# Pmod_DA4.net
KiCad netlist of a schematic drawn in Altium Designer
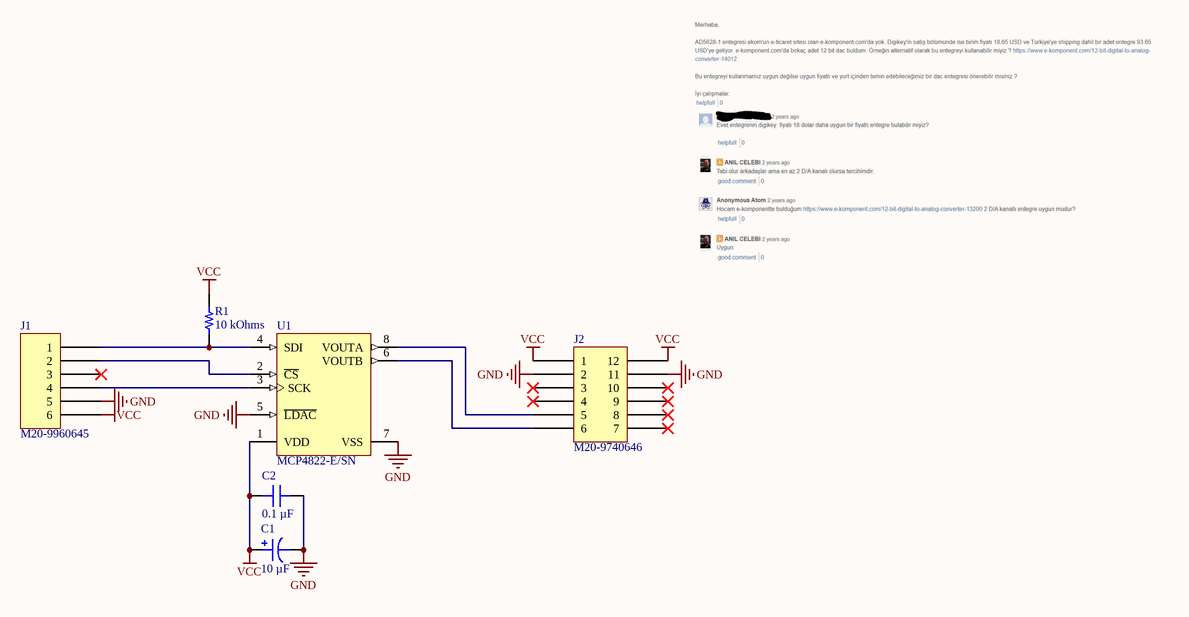
[diagram p0: Pmod_DA4.SchDoc]

(export (version "E")
  (design (tool "Eeschema 10.0.6"))
  (components
    (comp (ref "C1")
      (value "10 µF")
      (footprint "CAP POL 2917_7343")
      (description "CAP TANT 10UF 20% 50V 2917")
      (fields (field (name "PART NUMBER") "293D106X0050E2TE3") (field (name "MANUFACTURER") "Vishay Sprague"))
      (libsource (lib "Celestial Altium Library - altium_library") (part "Polarised Capacitor"))
    )
    (comp (ref "C2")
      (value "0.1 µF")
      (footprint "CAP 0805_2012")
      (description "CAP CER 0.1UF 50V X7R 0805")
      (fields (field (name "PART NUMBER") "CC0805MRX7R9BB104") (field (name "MANUFACTURER") "Yageo"))
      (libsource (lib "Celestial Altium Library - altium_library") (part "Capacitor"))
    )
    (comp (ref "J1")
      (value "M20-9960645")
      (footprint "HARWIN M20-9960645")
      (description "CONN HEADER R/A 6POS 2.54MM")
      (fields (field (name "MANUFACTURER") "Harwin Inc."))
      (libsource (lib "Celestial Altium Library - altium_library") (part "6 Pin"))
    )
    (comp (ref "J2")
      (value "M20-9740646")
      (footprint "HARWIN M20-9740645")
      (description "CONN HEADER R/A 12POS 2.54MM")
      (fields (field (name "MANUFACTURER") "Harwin Inc."))
      (libsource (lib "Celestial Altium Library - altium_library") (part "2X6 PIN DU"))
    )
    (comp (ref "R1")
      (value "10 kOhms")
      (footprint "RES 0805_2012")
      (description "TNPU0805 10K 0.05% 2PPM E52 E3")
      (fields (field (name "PART NUMBER") "TNPU080510K0AWEN00") (field (name "MANUFACTURER") "Vishay Dale"))
      (libsource (lib "Celestial Altium Library - altium_library") (part "Resistor"))
    )
    (comp (ref "U1")
      (value "MCP4822-E/SN")
      (footprint "SOIC-SN8_M")
      (description "12-Bit DACs with Internal VREF and SPI Interface, 8-Pin SOIC 150mil, Extended Temperature")
      (libsource (lib "Altium Content Vault") (part "CON-DAC-MCP4822-8"))
    )
  )
  (nets
    (net (code "1") (name "GND") (class "Default")
      (node (ref "C1") (pin "2") (pinfunction "2_2") (pintype "passive"))
      (node (ref "C2") (pin "1") (pinfunction "1_1") (pintype "passive"))
      (node (ref "J1") (pin "5") (pinfunction "5_5") (pintype "passive"))
      (node (ref "J2") (pin "11") (pinfunction "11_11") (pintype "passive"))
      (node (ref "J2") (pin "2") (pinfunction "2_2") (pintype "passive"))
      (node (ref "U1") (pin "5") (pinfunction "~{LDAC}_5") (pintype "input"))
      (node (ref "U1") (pin "7") (pinfunction "VSS_7") (pintype "power_in"))
    )
    (net (code "2") (name "Net-(U1-SCK)") (class "Default")
      (node (ref "J1") (pin "4") (pinfunction "4_4") (pintype "passive"))
      (node (ref "U1") (pin "3") (pinfunction "SCK_3") (pintype "input"))
    )
    (net (code "3") (name "Net-(U1-SDI)") (class "Default")
      (node (ref "J1") (pin "1") (pinfunction "1_1") (pintype "passive"))
      (node (ref "R1") (pin "1") (pinfunction "1_1") (pintype "passive"))
      (node (ref "U1") (pin "4") (pinfunction "SDI_4") (pintype "input"))
    )
    (net (code "4") (name "Net-(U1-VOUTA)") (class "Default")
      (node (ref "J2") (pin "5") (pinfunction "5_5") (pintype "passive"))
      (node (ref "U1") (pin "8") (pinfunction "VOUTA_8") (pintype "output"))
    )
    (net (code "5") (name "Net-(U1-VOUTB)") (class "Default")
      (node (ref "J2") (pin "6") (pinfunction "6_6") (pintype "passive"))
      (node (ref "U1") (pin "6") (pinfunction "VOUTB_6") (pintype "output"))
    )
    (net (code "6") (name "Net-(U1-~{CS})") (class "Default")
      (node (ref "J1") (pin "2") (pinfunction "2_2") (pintype "passive"))
      (node (ref "U1") (pin "2") (pinfunction "~{CS}_2") (pintype "input"))
    )
    (net (code "7") (name "VCC") (class "Default")
      (node (ref "C1") (pin "1") (pinfunction "1_1") (pintype "passive"))
      (node (ref "C2") (pin "2") (pinfunction "2_2") (pintype "passive"))
      (node (ref "J1") (pin "6") (pinfunction "6_6") (pintype "passive"))
      (node (ref "J2") (pin "1") (pinfunction "1_1") (pintype "passive"))
      (node (ref "J2") (pin "12") (pinfunction "12_12") (pintype "passive"))
      (node (ref "R1") (pin "2") (pinfunction "2_2") (pintype "passive"))
      (node (ref "U1") (pin "1") (pinfunction "VDD_1") (pintype "power_in"))
    )
    (net (code "8") (name "unconnected-(J1-Pad3)") (class "Default")
      (node (ref "J1") (pin "3") (pinfunction "3_3") (pintype "passive+no_connect"))
    )
    (net (code "9") (name "unconnected-(J2-Pad3)") (class "Default")
      (node (ref "J2") (pin "3") (pinfunction "3_3") (pintype "passive+no_connect"))
    )
    (net (code "10") (name "unconnected-(J2-Pad4)") (class "Default")
      (node (ref "J2") (pin "4") (pinfunction "4_4") (pintype "passive+no_connect"))
    )
    (net (code "11") (name "unconnected-(J2-Pad7)") (class "Default")
      (node (ref "J2") (pin "7") (pinfunction "7_7") (pintype "passive+no_connect"))
    )
    (net (code "12") (name "unconnected-(J2-Pad8)") (class "Default")
      (node (ref "J2") (pin "8") (pinfunction "8_8") (pintype "passive+no_connect"))
    )
    (net (code "13") (name "unconnected-(J2-Pad9)") (class "Default")
      (node (ref "J2") (pin "9") (pinfunction "9_9") (pintype "passive+no_connect"))
    )
    (net (code "14") (name "unconnected-(J2-Pad10)") (class "Default")
      (node (ref "J2") (pin "10") (pinfunction "10_10") (pintype "passive+no_connect"))
    )
  )
)
